# main_1.net
KiCad netlist of a schematic drawn in Altium Designer
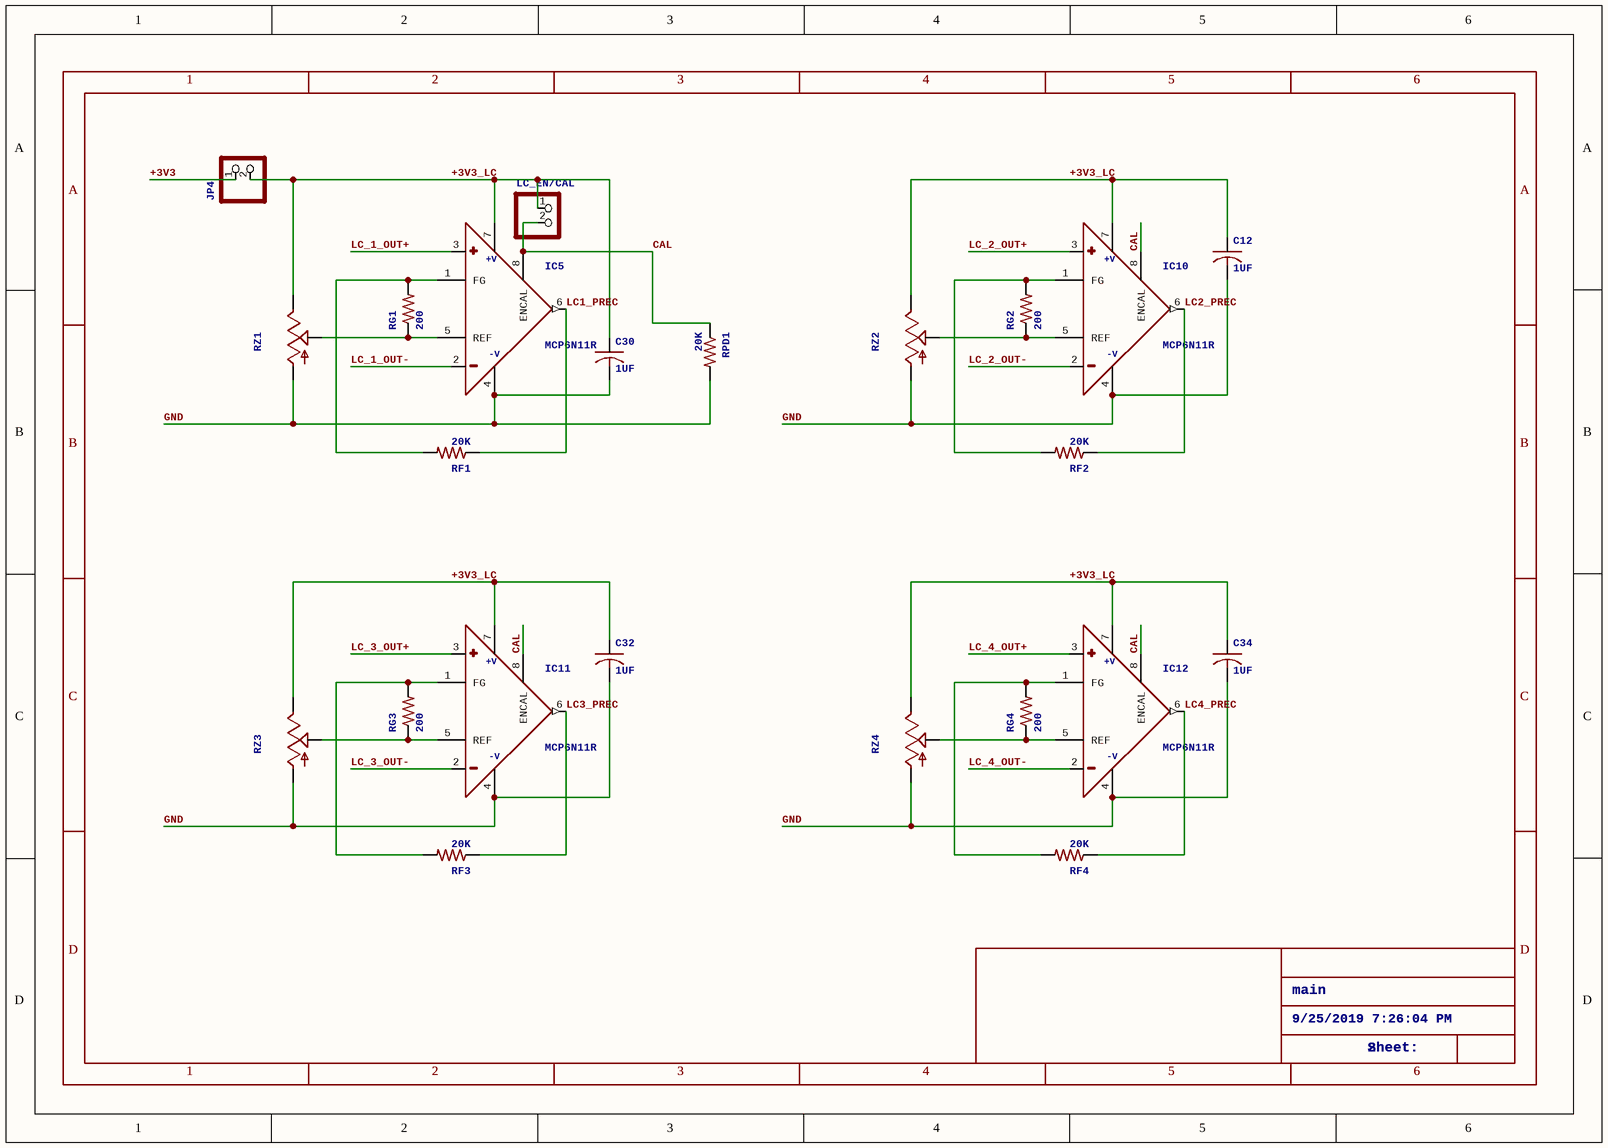
[diagram p0: main_1.SchDoc]

(export (version "E")
  (design (tool "Eeschema 10.0.6"))
  (components
    (comp (ref "C12")
      (value "1UF")
      (footprint "C0805")
      (description "CAPACITOR, American symbol")
      (libsource (lib "rcl") (part "C-USC0805"))
    )
    (comp (ref "C30")
      (value "1UF")
      (footprint "C0805")
      (description "CAPACITOR, American symbol")
      (libsource (lib "rcl") (part "C-USC0805"))
    )
    (comp (ref "C32")
      (value "1UF")
      (footprint "C0805")
      (description "CAPACITOR, American symbol")
      (libsource (lib "rcl") (part "C-USC0805"))
    )
    (comp (ref "C34")
      (value "1UF")
      (footprint "C0805")
      (description "CAPACITOR, American symbol")
      (libsource (lib "rcl") (part "C-USC0805"))
    )
    (comp (ref "IC5")
      (value "MCP6N11R")
      (footprint "SO-8")
      (fields
        (field (name "MPN") "AD620AR")
        (field (name "+V") "+V")
        (field (name "-V") "-V")
        (field (name "LIBRARYNAME") "microchip-extra")
      )
      (libsource (lib "microchip-extra") (part "MCP6N11R"))
    )
    (comp (ref "IC10")
      (value "MCP6N11R")
      (footprint "SO-8")
      (fields
        (field (name "MPN") "AD620AR")
        (field (name "+V") "+V")
        (field (name "-V") "-V")
        (field (name "LIBRARYNAME") "microchip-extra")
      )
      (libsource (lib "microchip-extra") (part "MCP6N11R"))
    )
    (comp (ref "IC11")
      (value "MCP6N11R")
      (footprint "SO-8")
      (fields
        (field (name "MPN") "AD620AR")
        (field (name "+V") "+V")
        (field (name "-V") "-V")
        (field (name "LIBRARYNAME") "microchip-extra")
      )
      (libsource (lib "microchip-extra") (part "MCP6N11R"))
    )
    (comp (ref "IC12")
      (value "MCP6N11R")
      (footprint "SO-8")
      (fields
        (field (name "MPN") "AD620AR")
        (field (name "+V") "+V")
        (field (name "-V") "-V")
        (field (name "LIBRARYNAME") "microchip-extra")
      )
      (libsource (lib "microchip-extra") (part "MCP6N11R"))
    )
    (comp (ref "JP4")
      (value "PINHD-1X2")
      (footprint "1X02")
      (description "PIN HEADER")
      (fields (field (name "LIBRARYNAME") "pinhead"))
      (libsource (lib "pinhead") (part "PINHD-1X2"))
    )
    (comp (ref "LC_EN/CAL")
      (value "PINHD-1X2")
      (footprint "1X02")
      (description "PIN HEADER")
      (fields (field (name "LIBRARYNAME") "pinhead"))
      (libsource (lib "pinhead") (part "PINHD-1X2"))
    )
    (comp (ref "RF1")
      (value "20K")
      (footprint "R0805")
      (description "RESISTOR, American symbol")
      (libsource (lib "rcl") (part "R-US_R0805"))
    )
    (comp (ref "RF2")
      (value "20K")
      (footprint "R0805")
      (description "RESISTOR, American symbol")
      (libsource (lib "rcl") (part "R-US_R0805"))
    )
    (comp (ref "RF3")
      (value "20K")
      (footprint "R0805")
      (description "RESISTOR, American symbol")
      (libsource (lib "rcl") (part "R-US_R0805"))
    )
    (comp (ref "RF4")
      (value "20K")
      (footprint "R0805")
      (description "RESISTOR, American symbol")
      (libsource (lib "rcl") (part "R-US_R0805"))
    )
    (comp (ref "RG1")
      (value "200")
      (footprint "R0805")
      (description "RESISTOR, American symbol")
      (libsource (lib "rcl") (part "R-US_R0805"))
    )
    (comp (ref "RG2")
      (value "200")
      (footprint "R0805")
      (description "RESISTOR, American symbol")
      (libsource (lib "rcl") (part "R-US_R0805"))
    )
    (comp (ref "RG3")
      (value "200")
      (footprint "R0805")
      (description "RESISTOR, American symbol")
      (libsource (lib "rcl") (part "R-US_R0805"))
    )
    (comp (ref "RG4")
      (value "200")
      (footprint "R0805")
      (description "RESISTOR, American symbol")
      (libsource (lib "rcl") (part "R-US_R0805"))
    )
    (comp (ref "RPD1")
      (value "20K")
      (footprint "R0805")
      (description "RESISTOR, American symbol")
      (libsource (lib "rcl") (part "R-US_R0805"))
    )
    (comp (ref "RZ1")
      (value "TRIM_US-S64W")
      (footprint "S64W")
      (description "POTENTIOMETER")
      (libsource (lib "pot") (part "TRIM_US-S64W"))
    )
    (comp (ref "RZ2")
      (value "TRIM_US-S64W")
      (footprint "S64W")
      (description "POTENTIOMETER")
      (libsource (lib "pot") (part "TRIM_US-S64W"))
    )
    (comp (ref "RZ3")
      (value "TRIM_US-S64W")
      (footprint "S64W")
      (description "POTENTIOMETER")
      (libsource (lib "pot") (part "TRIM_US-S64W"))
    )
    (comp (ref "RZ4")
      (value "TRIM_US-S64W")
      (footprint "S64W")
      (description "POTENTIOMETER")
      (libsource (lib "pot") (part "TRIM_US-S64W"))
    )
  )
  (nets
    (net (code "1") (name "/+3V3") (class "Default")
      (node (ref "JP4") (pin "1") (pinfunction "1_1") (pintype "passive"))
    )
    (net (code "2") (name "/+3V3_LC") (class "Default")
      (node (ref "C12") (pin "1") (pinfunction "1_1") (pintype "passive"))
      (node (ref "C30") (pin "1") (pinfunction "1_1") (pintype "passive"))
      (node (ref "C32") (pin "1") (pinfunction "1_1") (pintype "passive"))
      (node (ref "C34") (pin "1") (pinfunction "1_1") (pintype "passive"))
      (node (ref "IC10") (pin "7") (pinfunction "+V_7") (pintype "power_in"))
      (node (ref "IC11") (pin "7") (pinfunction "+V_7") (pintype "power_in"))
      (node (ref "IC12") (pin "7") (pinfunction "+V_7") (pintype "power_in"))
      (node (ref "IC5") (pin "7") (pinfunction "+V_7") (pintype "power_in"))
      (node (ref "JP4") (pin "2") (pinfunction "2_2") (pintype "passive"))
      (node (ref "LC_EN/CAL") (pin "1") (pinfunction "1_1") (pintype "passive"))
      (node (ref "RZ1") (pin "E") (pinfunction "E_E") (pintype "passive"))
      (node (ref "RZ2") (pin "E") (pinfunction "E_E") (pintype "passive"))
      (node (ref "RZ3") (pin "E") (pinfunction "E_E") (pintype "passive"))
      (node (ref "RZ4") (pin "E") (pinfunction "E_E") (pintype "passive"))
    )
    (net (code "3") (name "/CAL") (class "Default")
      (node (ref "IC10") (pin "8") (pinfunction "ENCAL_8") (pintype "passive"))
      (node (ref "IC11") (pin "8") (pinfunction "ENCAL_8") (pintype "passive"))
      (node (ref "IC12") (pin "8") (pinfunction "ENCAL_8") (pintype "passive"))
      (node (ref "IC5") (pin "8") (pinfunction "ENCAL_8") (pintype "passive"))
      (node (ref "LC_EN/CAL") (pin "2") (pinfunction "2_2") (pintype "passive"))
      (node (ref "RPD1") (pin "1") (pinfunction "1_1") (pintype "passive"))
    )
    (net (code "4") (name "/GND") (class "Default")
      (node (ref "C12") (pin "2") (pinfunction "2_2") (pintype "passive"))
      (node (ref "C30") (pin "2") (pinfunction "2_2") (pintype "passive"))
      (node (ref "C32") (pin "2") (pinfunction "2_2") (pintype "passive"))
      (node (ref "C34") (pin "2") (pinfunction "2_2") (pintype "passive"))
      (node (ref "IC10") (pin "4") (pinfunction "-V_4") (pintype "power_in"))
      (node (ref "IC11") (pin "4") (pinfunction "-V_4") (pintype "power_in"))
      (node (ref "IC12") (pin "4") (pinfunction "-V_4") (pintype "power_in"))
      (node (ref "IC5") (pin "4") (pinfunction "-V_4") (pintype "power_in"))
      (node (ref "RPD1") (pin "2") (pinfunction "2_2") (pintype "passive"))
      (node (ref "RZ1") (pin "A") (pinfunction "A_A") (pintype "passive"))
      (node (ref "RZ2") (pin "A") (pinfunction "A_A") (pintype "passive"))
      (node (ref "RZ3") (pin "A") (pinfunction "A_A") (pintype "passive"))
      (node (ref "RZ4") (pin "A") (pinfunction "A_A") (pintype "passive"))
    )
    (net (code "5") (name "/LC1_PREC") (class "Default")
      (node (ref "IC5") (pin "6") (pinfunction "OUT_6") (pintype "output"))
      (node (ref "RF1") (pin "1") (pinfunction "1_1") (pintype "passive"))
    )
    (net (code "6") (name "/LC2_PREC") (class "Default")
      (node (ref "IC10") (pin "6") (pinfunction "OUT_6") (pintype "output"))
      (node (ref "RF2") (pin "1") (pinfunction "1_1") (pintype "passive"))
    )
    (net (code "7") (name "/LC3_PREC") (class "Default")
      (node (ref "IC11") (pin "6") (pinfunction "OUT_6") (pintype "output"))
      (node (ref "RF3") (pin "1") (pinfunction "1_1") (pintype "passive"))
    )
    (net (code "8") (name "/LC4_PREC") (class "Default")
      (node (ref "IC12") (pin "6") (pinfunction "OUT_6") (pintype "output"))
      (node (ref "RF4") (pin "1") (pinfunction "1_1") (pintype "passive"))
    )
    (net (code "9") (name "/LC_1_OUT+") (class "Default")
      (node (ref "IC5") (pin "3") (pinfunction "+_3") (pintype "passive"))
    )
    (net (code "10") (name "/LC_1_OUT-") (class "Default")
      (node (ref "IC5") (pin "2") (pinfunction "-_2") (pintype "passive"))
    )
    (net (code "11") (name "/LC_2_OUT+") (class "Default")
      (node (ref "IC10") (pin "3") (pinfunction "+_3") (pintype "passive"))
    )
    (net (code "12") (name "/LC_2_OUT-") (class "Default")
      (node (ref "IC10") (pin "2") (pinfunction "-_2") (pintype "passive"))
    )
    (net (code "13") (name "/LC_3_OUT+") (class "Default")
      (node (ref "IC11") (pin "3") (pinfunction "+_3") (pintype "passive"))
    )
    (net (code "14") (name "/LC_3_OUT-") (class "Default")
      (node (ref "IC11") (pin "2") (pinfunction "-_2") (pintype "passive"))
    )
    (net (code "15") (name "/LC_4_OUT+") (class "Default")
      (node (ref "IC12") (pin "3") (pinfunction "+_3") (pintype "passive"))
    )
    (net (code "16") (name "/LC_4_OUT-") (class "Default")
      (node (ref "IC12") (pin "2") (pinfunction "-_2") (pintype "passive"))
    )
    (net (code "17") (name "Net-(IC5-FG)") (class "Default")
      (node (ref "IC5") (pin "1") (pinfunction "FG_1") (pintype "passive"))
      (node (ref "RF1") (pin "2") (pinfunction "2_2") (pintype "passive"))
      (node (ref "RG1") (pin "2") (pinfunction "2_2") (pintype "passive"))
    )
    (net (code "18") (name "Net-(IC5-REF)") (class "Default")
      (node (ref "IC5") (pin "5") (pinfunction "REF_5") (pintype "passive"))
      (node (ref "RG1") (pin "1") (pinfunction "1_1") (pintype "passive"))
      (node (ref "RZ1") (pin "S") (pinfunction "S_S") (pintype "passive"))
    )
    (net (code "19") (name "Net-(IC10-FG)") (class "Default")
      (node (ref "IC10") (pin "1") (pinfunction "FG_1") (pintype "passive"))
      (node (ref "RF2") (pin "2") (pinfunction "2_2") (pintype "passive"))
      (node (ref "RG2") (pin "2") (pinfunction "2_2") (pintype "passive"))
    )
    (net (code "20") (name "Net-(IC10-REF)") (class "Default")
      (node (ref "IC10") (pin "5") (pinfunction "REF_5") (pintype "passive"))
      (node (ref "RG2") (pin "1") (pinfunction "1_1") (pintype "passive"))
      (node (ref "RZ2") (pin "S") (pinfunction "S_S") (pintype "passive"))
    )
    (net (code "21") (name "Net-(IC11-FG)") (class "Default")
      (node (ref "IC11") (pin "1") (pinfunction "FG_1") (pintype "passive"))
      (node (ref "RF3") (pin "2") (pinfunction "2_2") (pintype "passive"))
      (node (ref "RG3") (pin "2") (pinfunction "2_2") (pintype "passive"))
    )
    (net (code "22") (name "Net-(IC11-REF)") (class "Default")
      (node (ref "IC11") (pin "5") (pinfunction "REF_5") (pintype "passive"))
      (node (ref "RG3") (pin "1") (pinfunction "1_1") (pintype "passive"))
      (node (ref "RZ3") (pin "S") (pinfunction "S_S") (pintype "passive"))
    )
    (net (code "23") (name "Net-(IC12-FG)") (class "Default")
      (node (ref "IC12") (pin "1") (pinfunction "FG_1") (pintype "passive"))
      (node (ref "RF4") (pin "2") (pinfunction "2_2") (pintype "passive"))
      (node (ref "RG4") (pin "2") (pinfunction "2_2") (pintype "passive"))
    )
    (net (code "24") (name "Net-(IC12-REF)") (class "Default")
      (node (ref "IC12") (pin "5") (pinfunction "REF_5") (pintype "passive"))
      (node (ref "RG4") (pin "1") (pinfunction "1_1") (pintype "passive"))
      (node (ref "RZ4") (pin "S") (pinfunction "S_S") (pintype "passive"))
    )
  )
)
